# Micromouse_controller_v005.net
KiCad netlist of a schematic drawn in EAGLE
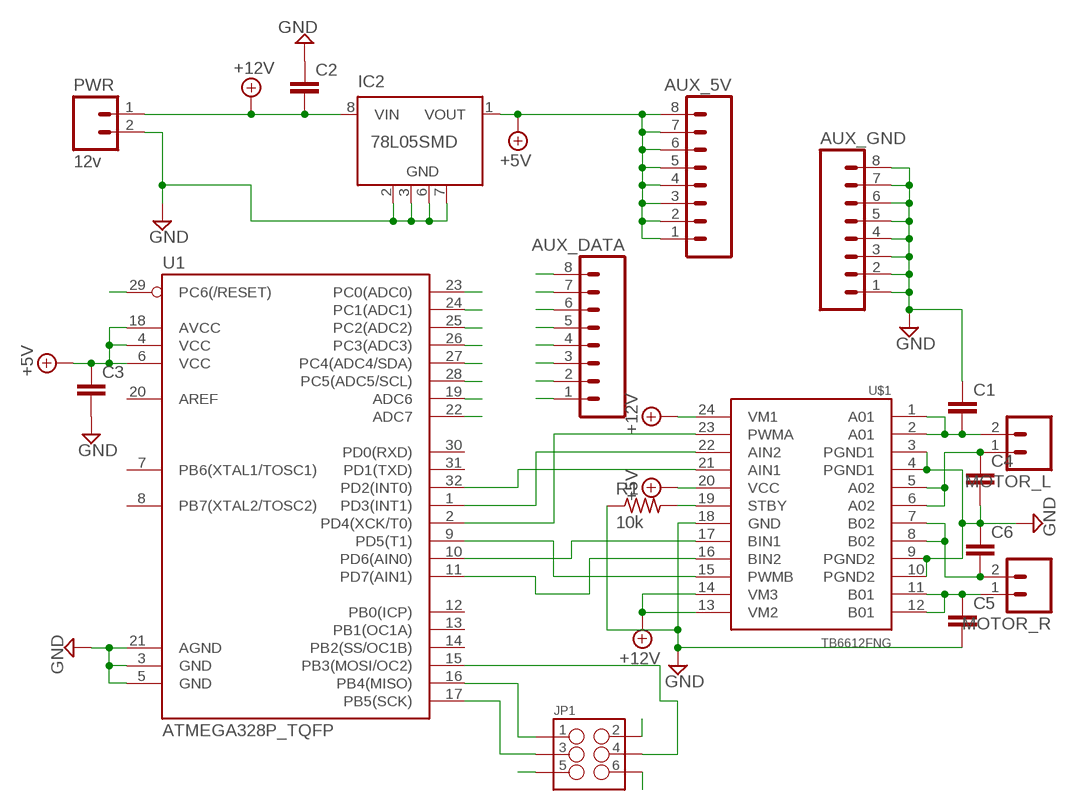
[diagram p0: schematic, sheet 1]

(export (version "E")
  (design (tool "Eeschema 10.0.6"))
  (components
    (comp (ref "AUX_5V")
      (value "M08SMD-STRAIGHT-ALT-FEMALE")
      (footprint "eagle-import:1X08_SMD_ALT")
      (libsource (lib "eagle-import") (part "M08SMD-STRAIGHT-ALT-FEMALE"))
    )
    (comp (ref "AUX_DATA")
      (value "M08SMD-STRAIGHT-ALT-FEMALE")
      (footprint "eagle-import:1X08_SMD_ALT")
      (libsource (lib "eagle-import") (part "M08SMD-STRAIGHT-ALT-FEMALE"))
    )
    (comp (ref "AUX_GND")
      (value "M08SMD-STRAIGHT-ALT-FEMALE")
      (footprint "eagle-import:1X08_SMD_ALT")
      (libsource (lib "eagle-import") (part "M08SMD-STRAIGHT-ALT-FEMALE"))
    )
    (comp (ref "C1")
      (value "CAPSMD")
      (footprint "eagle-import:GRM43D")
      (libsource (lib "eagle-import") (part "CAPSMD"))
    )
    (comp (ref "C2")
      (value "CAPSMD")
      (footprint "eagle-import:GRM43D")
      (libsource (lib "eagle-import") (part "CAPSMD"))
    )
    (comp (ref "C3")
      (value "CAPSMD")
      (footprint "eagle-import:GRM43D")
      (libsource (lib "eagle-import") (part "CAPSMD"))
    )
    (comp (ref "C4")
      (value "CAPSMD")
      (footprint "eagle-import:GRM43D")
      (libsource (lib "eagle-import") (part "CAPSMD"))
    )
    (comp (ref "C5")
      (value "CAPSMD")
      (footprint "eagle-import:GRM43D")
      (libsource (lib "eagle-import") (part "CAPSMD"))
    )
    (comp (ref "C6")
      (value "CAPSMD")
      (footprint "eagle-import:GRM43D")
      (libsource (lib "eagle-import") (part "CAPSMD"))
    )
    (comp (ref "IC2")
      (value "78L05SMD")
      (footprint "eagle-import:SO08")
      (libsource (lib "eagle-import") (part "78LSMD05"))
    )
    (comp (ref "JP1")
      (value "M03X2FEMALE_SMD")
      (footprint "eagle-import:2X3_SMD")
      (libsource (lib "eagle-import") (part "M03X2FEMALE_SMD"))
    )
    (comp (ref "MOTOR_L")
      (value "M02-JST-2MM-SMT")
      (footprint "eagle-import:JST-2-SMD")
      (libsource (lib "eagle-import") (part "M02-JST-2MM-SMT"))
    )
    (comp (ref "MOTOR_R")
      (value "M02-JST-2MM-SMT")
      (footprint "eagle-import:JST-2-SMD")
      (libsource (lib "eagle-import") (part "M02-JST-2MM-SMT"))
    )
    (comp (ref "PWR")
      (value "12v")
      (footprint "eagle-import:JST-2-SMD")
      (libsource (lib "eagle-import") (part "M02-JST-2MM-SMT"))
    )
    (comp (ref "R1")
      (value "10k")
      (footprint "eagle-import:R0603")
      (libsource (lib "eagle-import") (part "R-US_R0603"))
    )
    (comp (ref "U$1")
      (value "TB6612FNG")
      (footprint "eagle-import:SSOP24")
      (libsource (lib "eagle-import") (part "TB6612FNG"))
    )
    (comp (ref "U1")
      (value "ATMEGA328P_TQFP")
      (footprint "eagle-import:TQFP32-08")
      (libsource (lib "eagle-import") (part "ATMEGA328P_TQFP"))
    )
  )
  (nets
    (net (code "1") (name "+5V") (class "Default")
      (node (ref "AUX_5V") (pin "1") (pinfunction "1_1") (pintype "passive"))
      (node (ref "AUX_5V") (pin "2") (pinfunction "2_2") (pintype "passive"))
      (node (ref "AUX_5V") (pin "3") (pinfunction "3_3") (pintype "passive"))
      (node (ref "AUX_5V") (pin "4") (pinfunction "4_4") (pintype "passive"))
      (node (ref "AUX_5V") (pin "5") (pinfunction "5_5") (pintype "passive"))
      (node (ref "AUX_5V") (pin "6") (pinfunction "6_6") (pintype "passive"))
      (node (ref "AUX_5V") (pin "7") (pinfunction "7_7") (pintype "passive"))
      (node (ref "AUX_5V") (pin "8") (pinfunction "8_8") (pintype "passive"))
      (node (ref "C3") (pin "A") (pinfunction "1_A") (pintype "passive"))
      (node (ref "IC2") (pin "1") (pinfunction "VOUT_1") (pintype "output"))
      (node (ref "JP1") (pin "2") (pinfunction "2_2") (pintype "bidirectional"))
      (node (ref "U$1") (pin "20") (pinfunction "VCC_20") (pintype "bidirectional"))
      (node (ref "U1") (pin "18") (pinfunction "AVCC_18") (pintype "bidirectional"))
      (node (ref "U1") (pin "4") (pinfunction "VCC_4") (pintype "bidirectional"))
      (node (ref "U1") (pin "6") (pinfunction "VCC_6") (pintype "bidirectional"))
    )
    (net (code "2") (name "+12V") (class "Default")
      (node (ref "C2") (pin "C") (pinfunction "2_C") (pintype "passive"))
      (node (ref "IC2") (pin "8") (pinfunction "VIN_8") (pintype "passive"))
      (node (ref "PWR") (pin "1") (pinfunction "2_1") (pintype "passive"))
      (node (ref "U$1") (pin "13") (pinfunction "VM2_13") (pintype "bidirectional"))
      (node (ref "U$1") (pin "14") (pinfunction "VM3_14") (pintype "bidirectional"))
      (node (ref "U$1") (pin "24") (pinfunction "VM1_24") (pintype "bidirectional"))
    )
    (net (code "3") (name "/ADC0") (class "Default")
      (node (ref "AUX_DATA") (pin "3") (pinfunction "3_3") (pintype "passive"))
      (node (ref "U1") (pin "23") (pinfunction "PC0(ADC0)_23") (pintype "bidirectional"))
    )
    (net (code "4") (name "/ADC1") (class "Default")
      (node (ref "AUX_DATA") (pin "4") (pinfunction "4_4") (pintype "passive"))
      (node (ref "U1") (pin "24") (pinfunction "PC1(ADC1)_24") (pintype "bidirectional"))
    )
    (net (code "5") (name "/ADC2") (class "Default")
      (node (ref "AUX_DATA") (pin "5") (pinfunction "5_5") (pintype "passive"))
      (node (ref "U1") (pin "25") (pinfunction "PC2(ADC2)_25") (pintype "bidirectional"))
    )
    (net (code "6") (name "/ADC3") (class "Default")
      (node (ref "AUX_DATA") (pin "6") (pinfunction "6_6") (pintype "passive"))
      (node (ref "U1") (pin "26") (pinfunction "PC3(ADC3)_26") (pintype "bidirectional"))
    )
    (net (code "7") (name "/ADC4") (class "Default")
      (node (ref "AUX_DATA") (pin "7") (pinfunction "7_7") (pintype "passive"))
      (node (ref "U1") (pin "27") (pinfunction "PC4(ADC4/SDA)_27") (pintype "bidirectional"))
    )
    (net (code "8") (name "/ADC5") (class "Default")
      (node (ref "AUX_DATA") (pin "8") (pinfunction "8_8") (pintype "passive"))
      (node (ref "U1") (pin "28") (pinfunction "PC5(ADC5/SCL)_28") (pintype "bidirectional"))
    )
    (net (code "9") (name "/ADC6") (class "Default")
      (node (ref "AUX_DATA") (pin "1") (pinfunction "1_1") (pintype "passive"))
      (node (ref "U1") (pin "19") (pinfunction "ADC6_19") (pintype "bidirectional"))
    )
    (net (code "10") (name "/ADC7") (class "Default")
      (node (ref "AUX_DATA") (pin "2") (pinfunction "2_2") (pintype "passive"))
      (node (ref "U1") (pin "22") (pinfunction "ADC7_22") (pintype "bidirectional"))
    )
    (net (code "11") (name "/RST") (class "Default")
      (node (ref "JP1") (pin "5") (pinfunction "5_5") (pintype "bidirectional"))
      (node (ref "U1") (pin "29") (pinfunction "PC6(/RESET)_29") (pintype "bidirectional"))
    )
    (net (code "12") (name "GND") (class "Default")
      (node (ref "AUX_GND") (pin "1") (pinfunction "1_1") (pintype "passive"))
      (node (ref "AUX_GND") (pin "2") (pinfunction "2_2") (pintype "passive"))
      (node (ref "AUX_GND") (pin "3") (pinfunction "3_3") (pintype "passive"))
      (node (ref "AUX_GND") (pin "4") (pinfunction "4_4") (pintype "passive"))
      (node (ref "AUX_GND") (pin "5") (pinfunction "5_5") (pintype "passive"))
      (node (ref "AUX_GND") (pin "6") (pinfunction "6_6") (pintype "passive"))
      (node (ref "AUX_GND") (pin "7") (pinfunction "7_7") (pintype "passive"))
      (node (ref "AUX_GND") (pin "8") (pinfunction "8_8") (pintype "passive"))
      (node (ref "C1") (pin "A") (pinfunction "1_A") (pintype "passive"))
      (node (ref "C2") (pin "A") (pinfunction "1_A") (pintype "passive"))
      (node (ref "C3") (pin "C") (pinfunction "2_C") (pintype "passive"))
      (node (ref "C4") (pin "C") (pinfunction "2_C") (pintype "passive"))
      (node (ref "C5") (pin "C") (pinfunction "2_C") (pintype "passive"))
      (node (ref "C6") (pin "A") (pinfunction "1_A") (pintype "passive"))
      (node (ref "IC2") (pin "2") (pinfunction "GND_2") (pintype "power_in"))
      (node (ref "IC2") (pin "3") (pinfunction "GND_3") (pintype "power_in"))
      (node (ref "IC2") (pin "6") (pinfunction "GND_6") (pintype "power_in"))
      (node (ref "IC2") (pin "7") (pinfunction "GND_7") (pintype "power_in"))
      (node (ref "JP1") (pin "6") (pinfunction "6_6") (pintype "bidirectional"))
      (node (ref "PWR") (pin "2") (pinfunction "1_2") (pintype "passive"))
      (node (ref "R1") (pin "1") (pinfunction "1_1") (pintype "passive"))
      (node (ref "U$1") (pin "10") (pinfunction "PGND2_10") (pintype "bidirectional"))
      (node (ref "U$1") (pin "18") (pinfunction "GND_18") (pintype "bidirectional"))
      (node (ref "U$1") (pin "3") (pinfunction "PGND1_3") (pintype "bidirectional"))
      (node (ref "U$1") (pin "4") (pinfunction "PGND1_4") (pintype "bidirectional"))
      (node (ref "U$1") (pin "9") (pinfunction "PGND2_9") (pintype "bidirectional"))
      (node (ref "U1") (pin "21") (pinfunction "AGND_21") (pintype "bidirectional"))
      (node (ref "U1") (pin "3") (pinfunction "GND_3") (pintype "bidirectional"))
      (node (ref "U1") (pin "5") (pinfunction "GND_5") (pintype "bidirectional"))
    )
    (net (code "13") (name "Net-(C1-2)") (class "Default")
      (node (ref "C1") (pin "C") (pinfunction "2_C") (pintype "passive"))
      (node (ref "MOTOR_L") (pin "2") (pinfunction "1_2") (pintype "passive"))
      (node (ref "U$1") (pin "1") (pinfunction "A01_1") (pintype "bidirectional"))
      (node (ref "U$1") (pin "2") (pinfunction "A01_2") (pintype "bidirectional"))
    )
    (net (code "14") (name "Net-(C4-1)") (class "Default")
      (node (ref "C4") (pin "A") (pinfunction "1_A") (pintype "passive"))
      (node (ref "MOTOR_L") (pin "1") (pinfunction "2_1") (pintype "passive"))
      (node (ref "U$1") (pin "5") (pinfunction "A02_5") (pintype "bidirectional"))
      (node (ref "U$1") (pin "6") (pinfunction "A02_6") (pintype "bidirectional"))
    )
    (net (code "15") (name "Net-(C5-1)") (class "Default")
      (node (ref "C5") (pin "A") (pinfunction "1_A") (pintype "passive"))
      (node (ref "MOTOR_R") (pin "1") (pinfunction "2_1") (pintype "passive"))
      (node (ref "U$1") (pin "11") (pinfunction "B01_11") (pintype "bidirectional"))
      (node (ref "U$1") (pin "12") (pinfunction "B01_12") (pintype "bidirectional"))
    )
    (net (code "16") (name "Net-(C6-2)") (class "Default")
      (node (ref "C6") (pin "C") (pinfunction "2_C") (pintype "passive"))
      (node (ref "MOTOR_R") (pin "2") (pinfunction "1_2") (pintype "passive"))
      (node (ref "U$1") (pin "7") (pinfunction "B02_7") (pintype "bidirectional"))
      (node (ref "U$1") (pin "8") (pinfunction "B02_8") (pintype "bidirectional"))
    )
    (net (code "17") (name "Net-(U$1-AIN1)") (class "Default")
      (node (ref "U$1") (pin "21") (pinfunction "AIN1_21") (pintype "bidirectional"))
      (node (ref "U1") (pin "32") (pinfunction "PD2(INT0)_32") (pintype "bidirectional"))
    )
    (net (code "18") (name "Net-(U$1-AIN2)") (class "Default")
      (node (ref "U$1") (pin "22") (pinfunction "AIN2_22") (pintype "bidirectional"))
      (node (ref "U1") (pin "1") (pinfunction "PD3(INT1)_1") (pintype "bidirectional"))
    )
    (net (code "19") (name "Net-(U$1-BIN1)") (class "Default")
      (node (ref "U$1") (pin "17") (pinfunction "BIN1_17") (pintype "bidirectional"))
      (node (ref "U1") (pin "10") (pinfunction "PD6(AIN0)_10") (pintype "bidirectional"))
    )
    (net (code "20") (name "Net-(U$1-BIN2)") (class "Default")
      (node (ref "U$1") (pin "16") (pinfunction "BIN2_16") (pintype "bidirectional"))
      (node (ref "U1") (pin "11") (pinfunction "PD7(AIN1)_11") (pintype "bidirectional"))
    )
    (net (code "21") (name "Net-(U$1-PWMA)") (class "Default")
      (node (ref "U$1") (pin "23") (pinfunction "PWMA_23") (pintype "bidirectional"))
      (node (ref "U1") (pin "2") (pinfunction "PD4(XCK/T0)_2") (pintype "bidirectional"))
    )
    (net (code "22") (name "Net-(U$1-PWMB)") (class "Default")
      (node (ref "U$1") (pin "15") (pinfunction "PWMB_15") (pintype "bidirectional"))
      (node (ref "U1") (pin "9") (pinfunction "PD5(T1)_9") (pintype "bidirectional"))
    )
    (net (code "23") (name "Net-(U$1-STBY)") (class "Default")
      (node (ref "R1") (pin "2") (pinfunction "2_2") (pintype "passive"))
      (node (ref "U$1") (pin "19") (pinfunction "STBY_19") (pintype "bidirectional"))
    )
    (net (code "24") (name "Net-(U1-PB3(MOSI{slash}OC2))") (class "Default")
      (node (ref "JP1") (pin "4") (pinfunction "4_4") (pintype "bidirectional"))
      (node (ref "U1") (pin "15") (pinfunction "PB3(MOSI/OC2)_15") (pintype "bidirectional"))
    )
    (net (code "25") (name "Net-(U1-PB4(MISO))") (class "Default")
      (node (ref "JP1") (pin "1") (pinfunction "1_1") (pintype "bidirectional"))
      (node (ref "U1") (pin "16") (pinfunction "PB4(MISO)_16") (pintype "bidirectional"))
    )
    (net (code "26") (name "Net-(U1-PB5(SCK))") (class "Default")
      (node (ref "JP1") (pin "3") (pinfunction "3_3") (pintype "bidirectional"))
      (node (ref "U1") (pin "17") (pinfunction "PB5(SCK)_17") (pintype "bidirectional"))
    )
    (net (code "27") (name "unconnected-(U1-AREF-Pad20)") (class "Default")
      (node (ref "U1") (pin "20") (pinfunction "AREF_20") (pintype "bidirectional"))
    )
    (net (code "28") (name "unconnected-(U1-PB0(ICP)-Pad12)") (class "Default")
      (node (ref "U1") (pin "12") (pinfunction "PB0(ICP)_12") (pintype "bidirectional"))
    )
    (net (code "29") (name "unconnected-(U1-PB1(OC1A)-Pad13)") (class "Default")
      (node (ref "U1") (pin "13") (pinfunction "PB1(OC1A)_13") (pintype "bidirectional"))
    )
    (net (code "30") (name "unconnected-(U1-PB2(SS{slash}OC1B)-Pad14)") (class "Default")
      (node (ref "U1") (pin "14") (pinfunction "PB2(SS/OC1B)_14") (pintype "bidirectional"))
    )
    (net (code "31") (name "unconnected-(U1-PB6(XTAL1{slash}TOSC1)-Pad7)") (class "Default")
      (node (ref "U1") (pin "7") (pinfunction "PB6(XTAL1/TOSC1)_7") (pintype "bidirectional"))
    )
    (net (code "32") (name "unconnected-(U1-PB7(XTAL2{slash}TOSC2)-Pad8)") (class "Default")
      (node (ref "U1") (pin "8") (pinfunction "PB7(XTAL2/TOSC2)_8") (pintype "bidirectional"))
    )
    (net (code "33") (name "unconnected-(U1-PD0(RXD)-Pad30)") (class "Default")
      (node (ref "U1") (pin "30") (pinfunction "PD0(RXD)_30") (pintype "bidirectional"))
    )
    (net (code "34") (name "unconnected-(U1-PD1(TXD)-Pad31)") (class "Default")
      (node (ref "U1") (pin "31") (pinfunction "PD1(TXD)_31") (pintype "bidirectional"))
    )
  )
)
